# OP2_1.net
KiCad netlist of a schematic drawn in EasyEDA
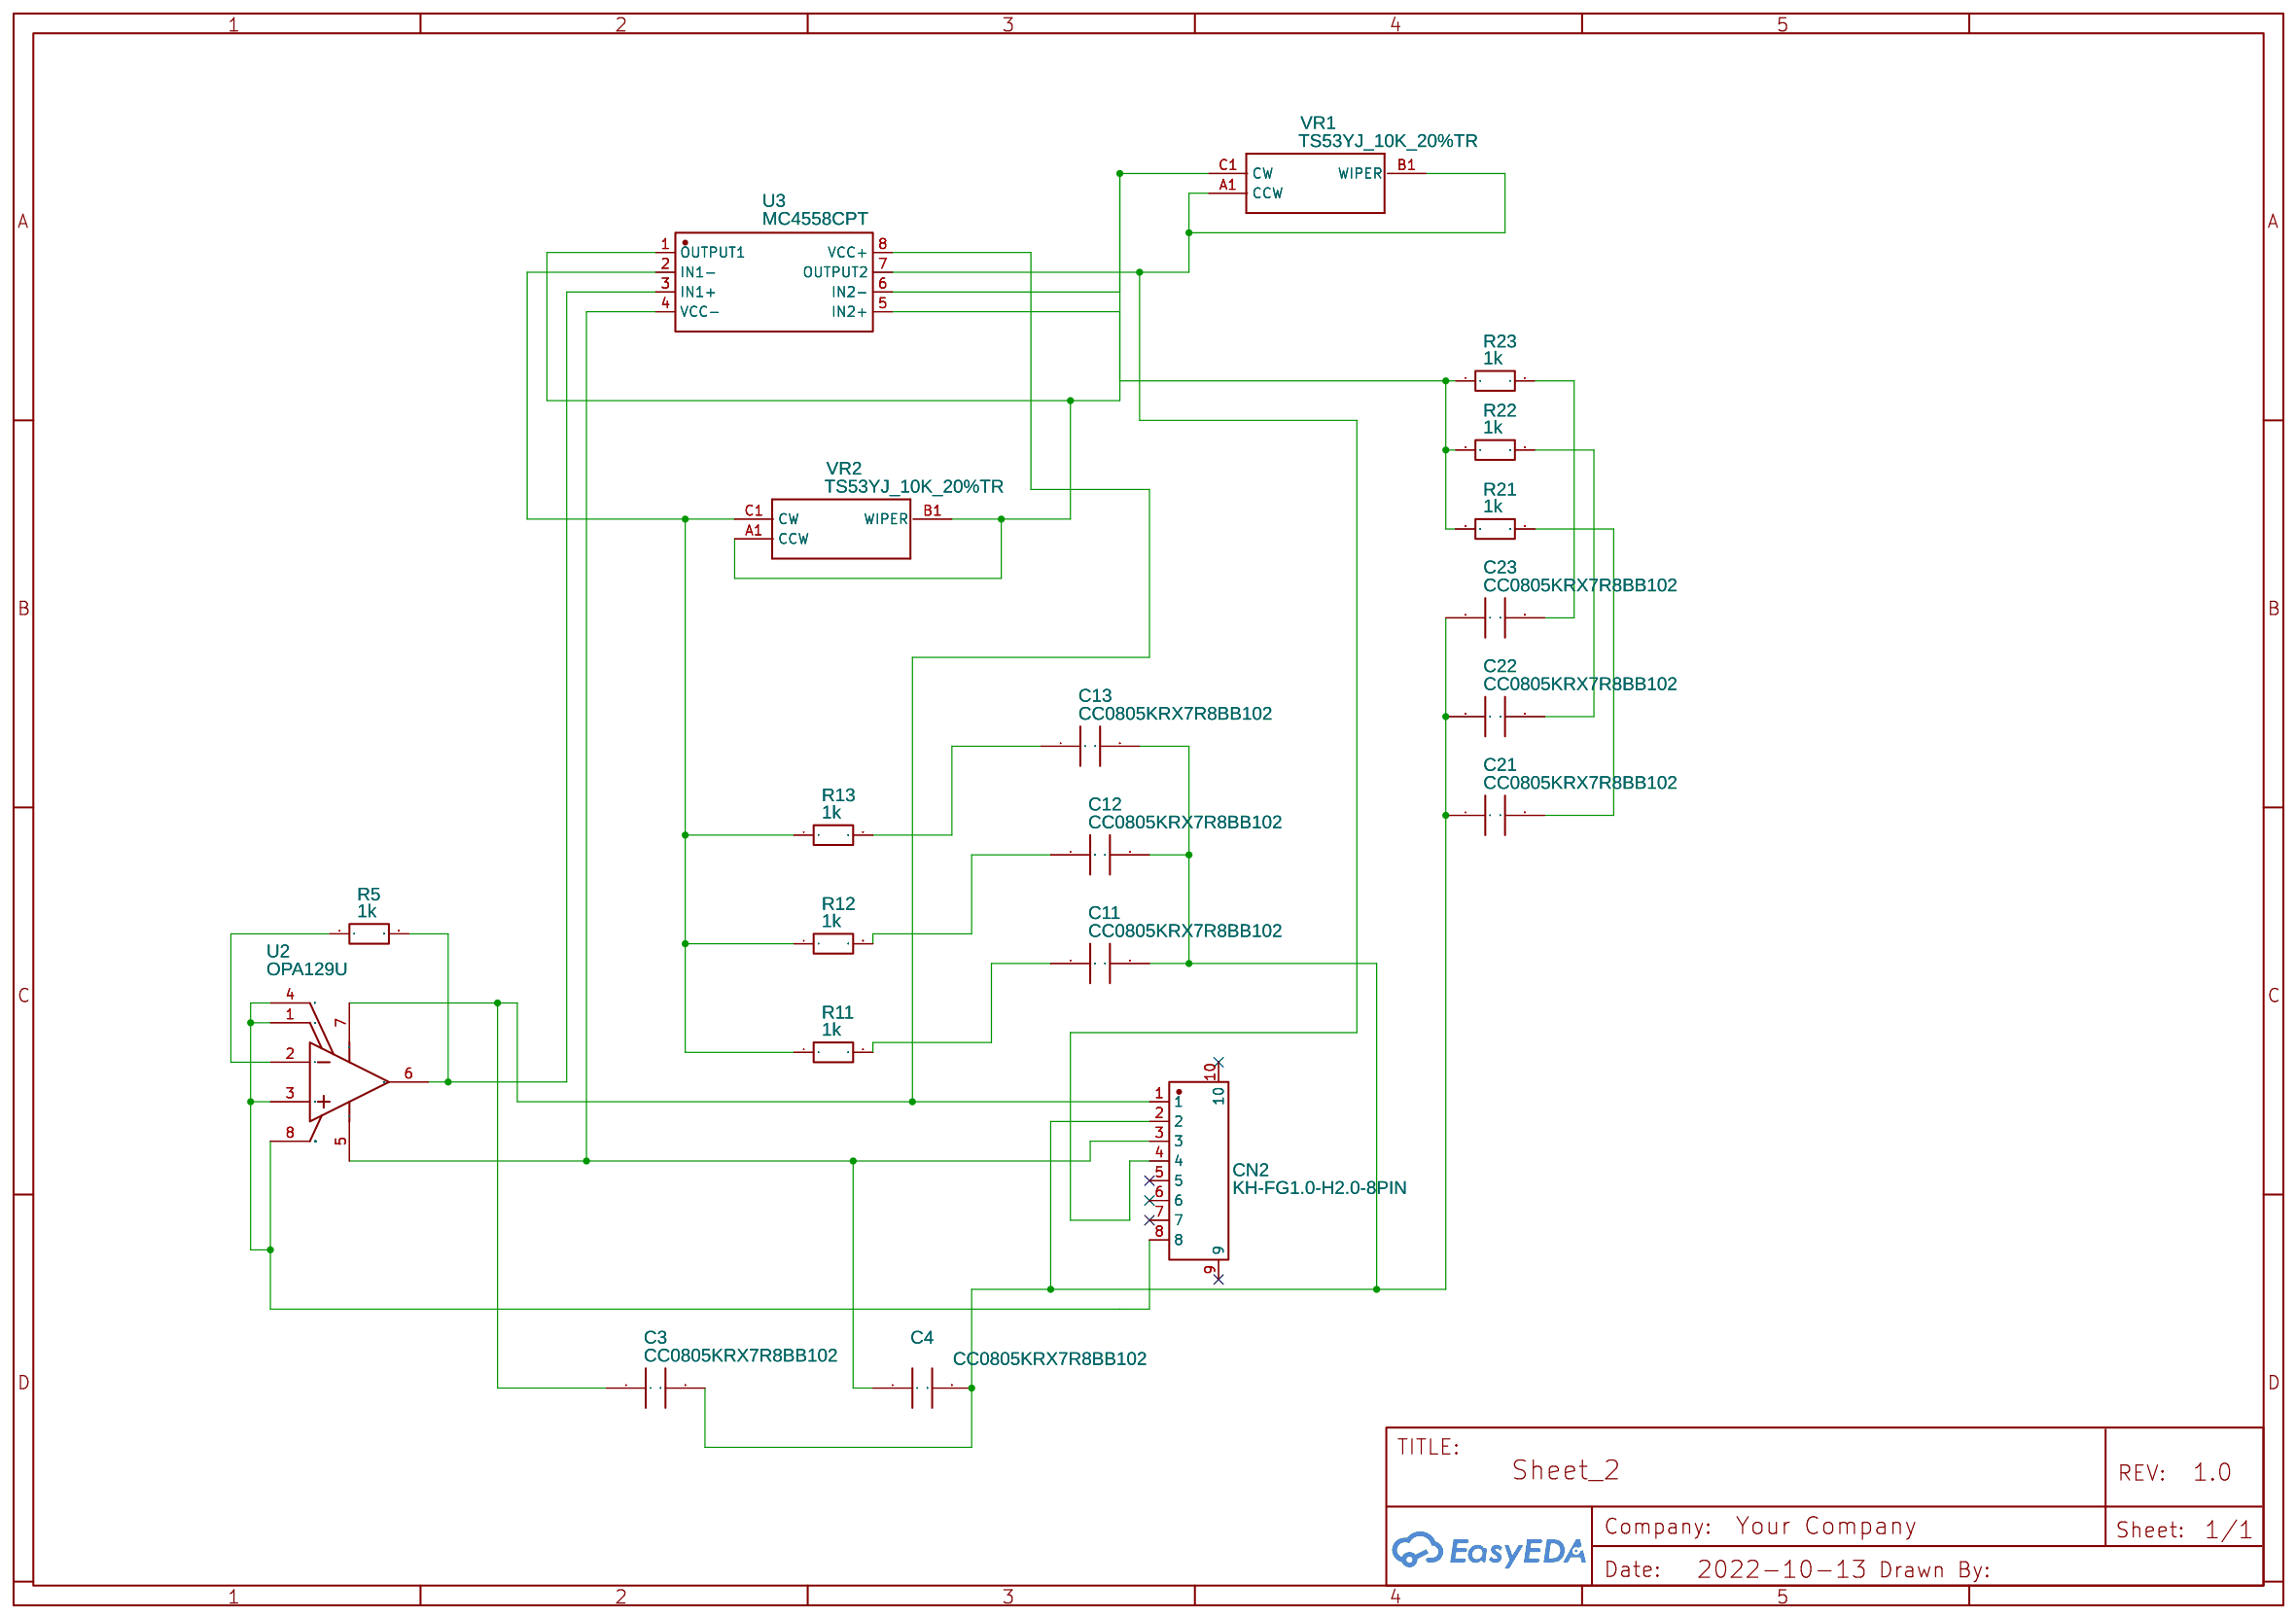
[diagram p0: schematic sheet]

(export (version "E")
  (design (tool "Eeschema 10.0.6"))
  (components
    (comp (ref "C3")
      (value "CC0805KRX7R8BB102")
      (fields (field (name "BOM_Supplier Part") "311-4314-1-ND"))
      (libsource (lib "") (part "CC0805KRX7R8BB102"))
    )
    (comp (ref "C4")
      (value "CC0805KRX7R8BB102")
      (fields (field (name "BOM_Supplier Part") "311-4314-1-ND"))
      (libsource (lib "") (part "CC0805KRX7R8BB102"))
    )
    (comp (ref "C11")
      (value "CC0805KRX7R8BB102")
      (fields (field (name "BOM_Supplier Part") "311-4314-1-ND"))
      (libsource (lib "") (part "CC0805KRX7R8BB102"))
    )
    (comp (ref "C12")
      (value "CC0805KRX7R8BB102")
      (fields (field (name "BOM_Supplier Part") "311-4314-1-ND"))
      (libsource (lib "") (part "CC0805KRX7R8BB102"))
    )
    (comp (ref "C13")
      (value "CC0805KRX7R8BB102")
      (fields (field (name "BOM_Supplier Part") "311-4314-1-ND"))
      (libsource (lib "") (part "CC0805KRX7R8BB102"))
    )
    (comp (ref "C21")
      (value "CC0805KRX7R8BB102")
      (fields (field (name "BOM_Supplier Part") "311-4314-1-ND"))
      (libsource (lib "") (part "CC0805KRX7R8BB102"))
    )
    (comp (ref "C22")
      (value "CC0805KRX7R8BB102")
      (fields (field (name "BOM_Supplier Part") "311-4314-1-ND"))
      (libsource (lib "") (part "CC0805KRX7R8BB102"))
    )
    (comp (ref "C23")
      (value "CC0805KRX7R8BB102")
      (fields (field (name "BOM_Supplier Part") "311-4314-1-ND"))
      (libsource (lib "") (part "CC0805KRX7R8BB102"))
    )
    (comp (ref "CN2")
      (value "KH-FG1.0-H2.0-8PIN")
      (fields (field (name "BOM_Supplier Part") "C2797225"))
      (libsource (lib "") (part "KH-FG1.0-H2.0-8PIN"))
    )
    (comp (ref "R5") (value "1k") (libsource (lib "") (part "R_0603_EU")))
    (comp (ref "R11") (value "1k") (libsource (lib "") (part "R_0603_EU")))
    (comp (ref "R12") (value "1k") (libsource (lib "") (part "R_0603_EU")))
    (comp (ref "R13") (value "1k") (libsource (lib "") (part "R_0603_EU")))
    (comp (ref "R21") (value "1k") (libsource (lib "") (part "R_0603_EU")))
    (comp (ref "R22") (value "1k") (libsource (lib "") (part "R_0603_EU")))
    (comp (ref "R23") (value "1k") (libsource (lib "") (part "R_0603_EU")))
    (comp (ref "U2")
      (value "OPA129U")
      (fields (field (name "BOM_Supplier Part") "C56181"))
      (libsource (lib "") (part "OPA129U"))
    )
    (comp (ref "U3")
      (value "MC4558CPT")
      (fields (field (name "BOM_Supplier Part") "C283326"))
      (libsource (lib "") (part "MC4558CPT"))
    )
    (comp (ref "VR1") (value "TS53YJ_10K_20%TR") (libsource (lib "") (part "TS53YJ_10K_20%TR")))
    (comp (ref "VR2") (value "TS53YJ_10K_20%TR") (libsource (lib "") (part "TS53YJ_10K_20%TR")))
  )
  (nets
    (net (code "1") (name "Net-(C11-Pad1)") (class "Default")
      (node (ref "C11") (pin "1") (pinfunction "1_1") (pintype "unspecified"))
      (node (ref "R11") (pin "2") (pinfunction "2_2") (pintype "unspecified"))
    )
    (net (code "2") (name "Net-(C11-Pad2)") (class "Default")
      (node (ref "C11") (pin "2") (pinfunction "2_2") (pintype "unspecified"))
      (node (ref "C12") (pin "2") (pinfunction "2_2") (pintype "unspecified"))
      (node (ref "C13") (pin "2") (pinfunction "2_2") (pintype "unspecified"))
      (node (ref "C21") (pin "1") (pinfunction "1_1") (pintype "unspecified"))
      (node (ref "C22") (pin "1") (pinfunction "1_1") (pintype "unspecified"))
      (node (ref "C23") (pin "1") (pinfunction "1_1") (pintype "unspecified"))
      (node (ref "C3") (pin "2") (pinfunction "2_2") (pintype "unspecified"))
      (node (ref "C4") (pin "2") (pinfunction "2_2") (pintype "unspecified"))
      (node (ref "CN2") (pin "2") (pinfunction "2_2") (pintype "unspecified"))
    )
    (net (code "3") (name "Net-(C12-Pad1)") (class "Default")
      (node (ref "C12") (pin "1") (pinfunction "1_1") (pintype "unspecified"))
      (node (ref "R12") (pin "2") (pinfunction "2_2") (pintype "unspecified"))
    )
    (net (code "4") (name "Net-(C13-Pad1)") (class "Default")
      (node (ref "C13") (pin "1") (pinfunction "1_1") (pintype "unspecified"))
      (node (ref "R13") (pin "2") (pinfunction "2_2") (pintype "unspecified"))
    )
    (net (code "5") (name "Net-(C21-Pad2)") (class "Default")
      (node (ref "C21") (pin "2") (pinfunction "2_2") (pintype "unspecified"))
      (node (ref "R21") (pin "2") (pinfunction "2_2") (pintype "unspecified"))
    )
    (net (code "6") (name "Net-(C22-Pad2)") (class "Default")
      (node (ref "C22") (pin "2") (pinfunction "2_2") (pintype "unspecified"))
      (node (ref "R22") (pin "2") (pinfunction "2_2") (pintype "unspecified"))
    )
    (net (code "7") (name "Net-(C23-Pad2)") (class "Default")
      (node (ref "C23") (pin "2") (pinfunction "2_2") (pintype "unspecified"))
      (node (ref "R23") (pin "2") (pinfunction "2_2") (pintype "unspecified"))
    )
    (net (code "8") (name "Net-(U2-IN+)") (class "Default")
      (node (ref "CN2") (pin "8") (pinfunction "8_8") (pintype "unspecified"))
      (node (ref "U2") (pin "1") (pinfunction "NC_1") (pintype "unspecified"))
      (node (ref "U2") (pin "3") (pinfunction "IN+_3") (pintype "unspecified"))
      (node (ref "U2") (pin "4") (pinfunction "NC_4") (pintype "unspecified"))
      (node (ref "U2") (pin "8") (pinfunction "SUBSTRATE_8") (pintype "unspecified"))
    )
    (net (code "9") (name "Net-(U2-IN-)") (class "Default")
      (node (ref "R5") (pin "1") (pinfunction "1_1") (pintype "unspecified"))
      (node (ref "U2") (pin "2") (pinfunction "IN-_2") (pintype "unspecified"))
    )
    (net (code "10") (name "Net-(U2-OUT)") (class "Default")
      (node (ref "R5") (pin "2") (pinfunction "2_2") (pintype "unspecified"))
      (node (ref "U2") (pin "6") (pinfunction "OUT_6") (pintype "output"))
      (node (ref "U3") (pin "3") (pinfunction "IN1+_3") (pintype "unspecified"))
    )
    (net (code "11") (name "Net-(U2-V+)") (class "Default")
      (node (ref "C3") (pin "1") (pinfunction "1_1") (pintype "unspecified"))
      (node (ref "CN2") (pin "1") (pinfunction "1_1") (pintype "unspecified"))
      (node (ref "U2") (pin "7") (pinfunction "V+_7") (pintype "passive"))
      (node (ref "U3") (pin "8") (pinfunction "VCC+_8") (pintype "unspecified"))
    )
    (net (code "12") (name "Net-(U2-V-)") (class "Default")
      (node (ref "C4") (pin "1") (pinfunction "1_1") (pintype "unspecified"))
      (node (ref "CN2") (pin "3") (pinfunction "3_3") (pintype "unspecified"))
      (node (ref "U2") (pin "5") (pinfunction "V-_5") (pintype "passive"))
      (node (ref "U3") (pin "4") (pinfunction "VCC-_4") (pintype "unspecified"))
    )
    (net (code "13") (name "Net-(U3-IN1-)") (class "Default")
      (node (ref "R11") (pin "1") (pinfunction "1_1") (pintype "unspecified"))
      (node (ref "R12") (pin "1") (pinfunction "1_1") (pintype "unspecified"))
      (node (ref "R13") (pin "1") (pinfunction "1_1") (pintype "unspecified"))
      (node (ref "U3") (pin "2") (pinfunction "IN1-_2") (pintype "unspecified"))
      (node (ref "VR2") (pin "C1") (pinfunction "CW_C1") (pintype "bidirectional"))
    )
    (net (code "14") (name "Net-(U3-IN2+)") (class "Default")
      (node (ref "U3") (pin "1") (pinfunction "OUTPUT1_1") (pintype "unspecified"))
      (node (ref "U3") (pin "5") (pinfunction "IN2+_5") (pintype "unspecified"))
      (node (ref "VR2") (pin "A1") (pinfunction "CCW_A1") (pintype "bidirectional"))
      (node (ref "VR2") (pin "B1") (pinfunction "WIPER_B1") (pintype "bidirectional"))
    )
    (net (code "15") (name "Net-(U3-IN2-)") (class "Default")
      (node (ref "R21") (pin "1") (pinfunction "1_1") (pintype "unspecified"))
      (node (ref "R22") (pin "1") (pinfunction "1_1") (pintype "unspecified"))
      (node (ref "R23") (pin "1") (pinfunction "1_1") (pintype "unspecified"))
      (node (ref "U3") (pin "6") (pinfunction "IN2-_6") (pintype "unspecified"))
      (node (ref "VR1") (pin "C1") (pinfunction "CW_C1") (pintype "bidirectional"))
    )
    (net (code "16") (name "Net-(U3-OUTPUT2)") (class "Default")
      (node (ref "CN2") (pin "4") (pinfunction "4_4") (pintype "unspecified"))
      (node (ref "U3") (pin "7") (pinfunction "OUTPUT2_7") (pintype "unspecified"))
      (node (ref "VR1") (pin "A1") (pinfunction "CCW_A1") (pintype "bidirectional"))
      (node (ref "VR1") (pin "B1") (pinfunction "WIPER_B1") (pintype "bidirectional"))
    )
    (net (code "17") (name "unconnected-(CN2-Pad5)") (class "Default")
      (node (ref "CN2") (pin "5") (pinfunction "5_5") (pintype "unspecified+no_connect"))
    )
    (net (code "18") (name "unconnected-(CN2-Pad6)") (class "Default")
      (node (ref "CN2") (pin "6") (pinfunction "6_6") (pintype "unspecified+no_connect"))
    )
    (net (code "19") (name "unconnected-(CN2-Pad7)") (class "Default")
      (node (ref "CN2") (pin "7") (pinfunction "7_7") (pintype "unspecified+no_connect"))
    )
    (net (code "20") (name "unconnected-(CN2-Pad9)") (class "Default")
      (node (ref "CN2") (pin "9") (pinfunction "9_9") (pintype "unspecified+no_connect"))
    )
    (net (code "21") (name "unconnected-(CN2-Pad10)") (class "Default")
      (node (ref "CN2") (pin "10") (pinfunction "10_10") (pintype "unspecified+no_connect"))
    )
  )
)
